# NRV-AOU34.net
KiCad netlist of a schematic drawn in Altium Designer
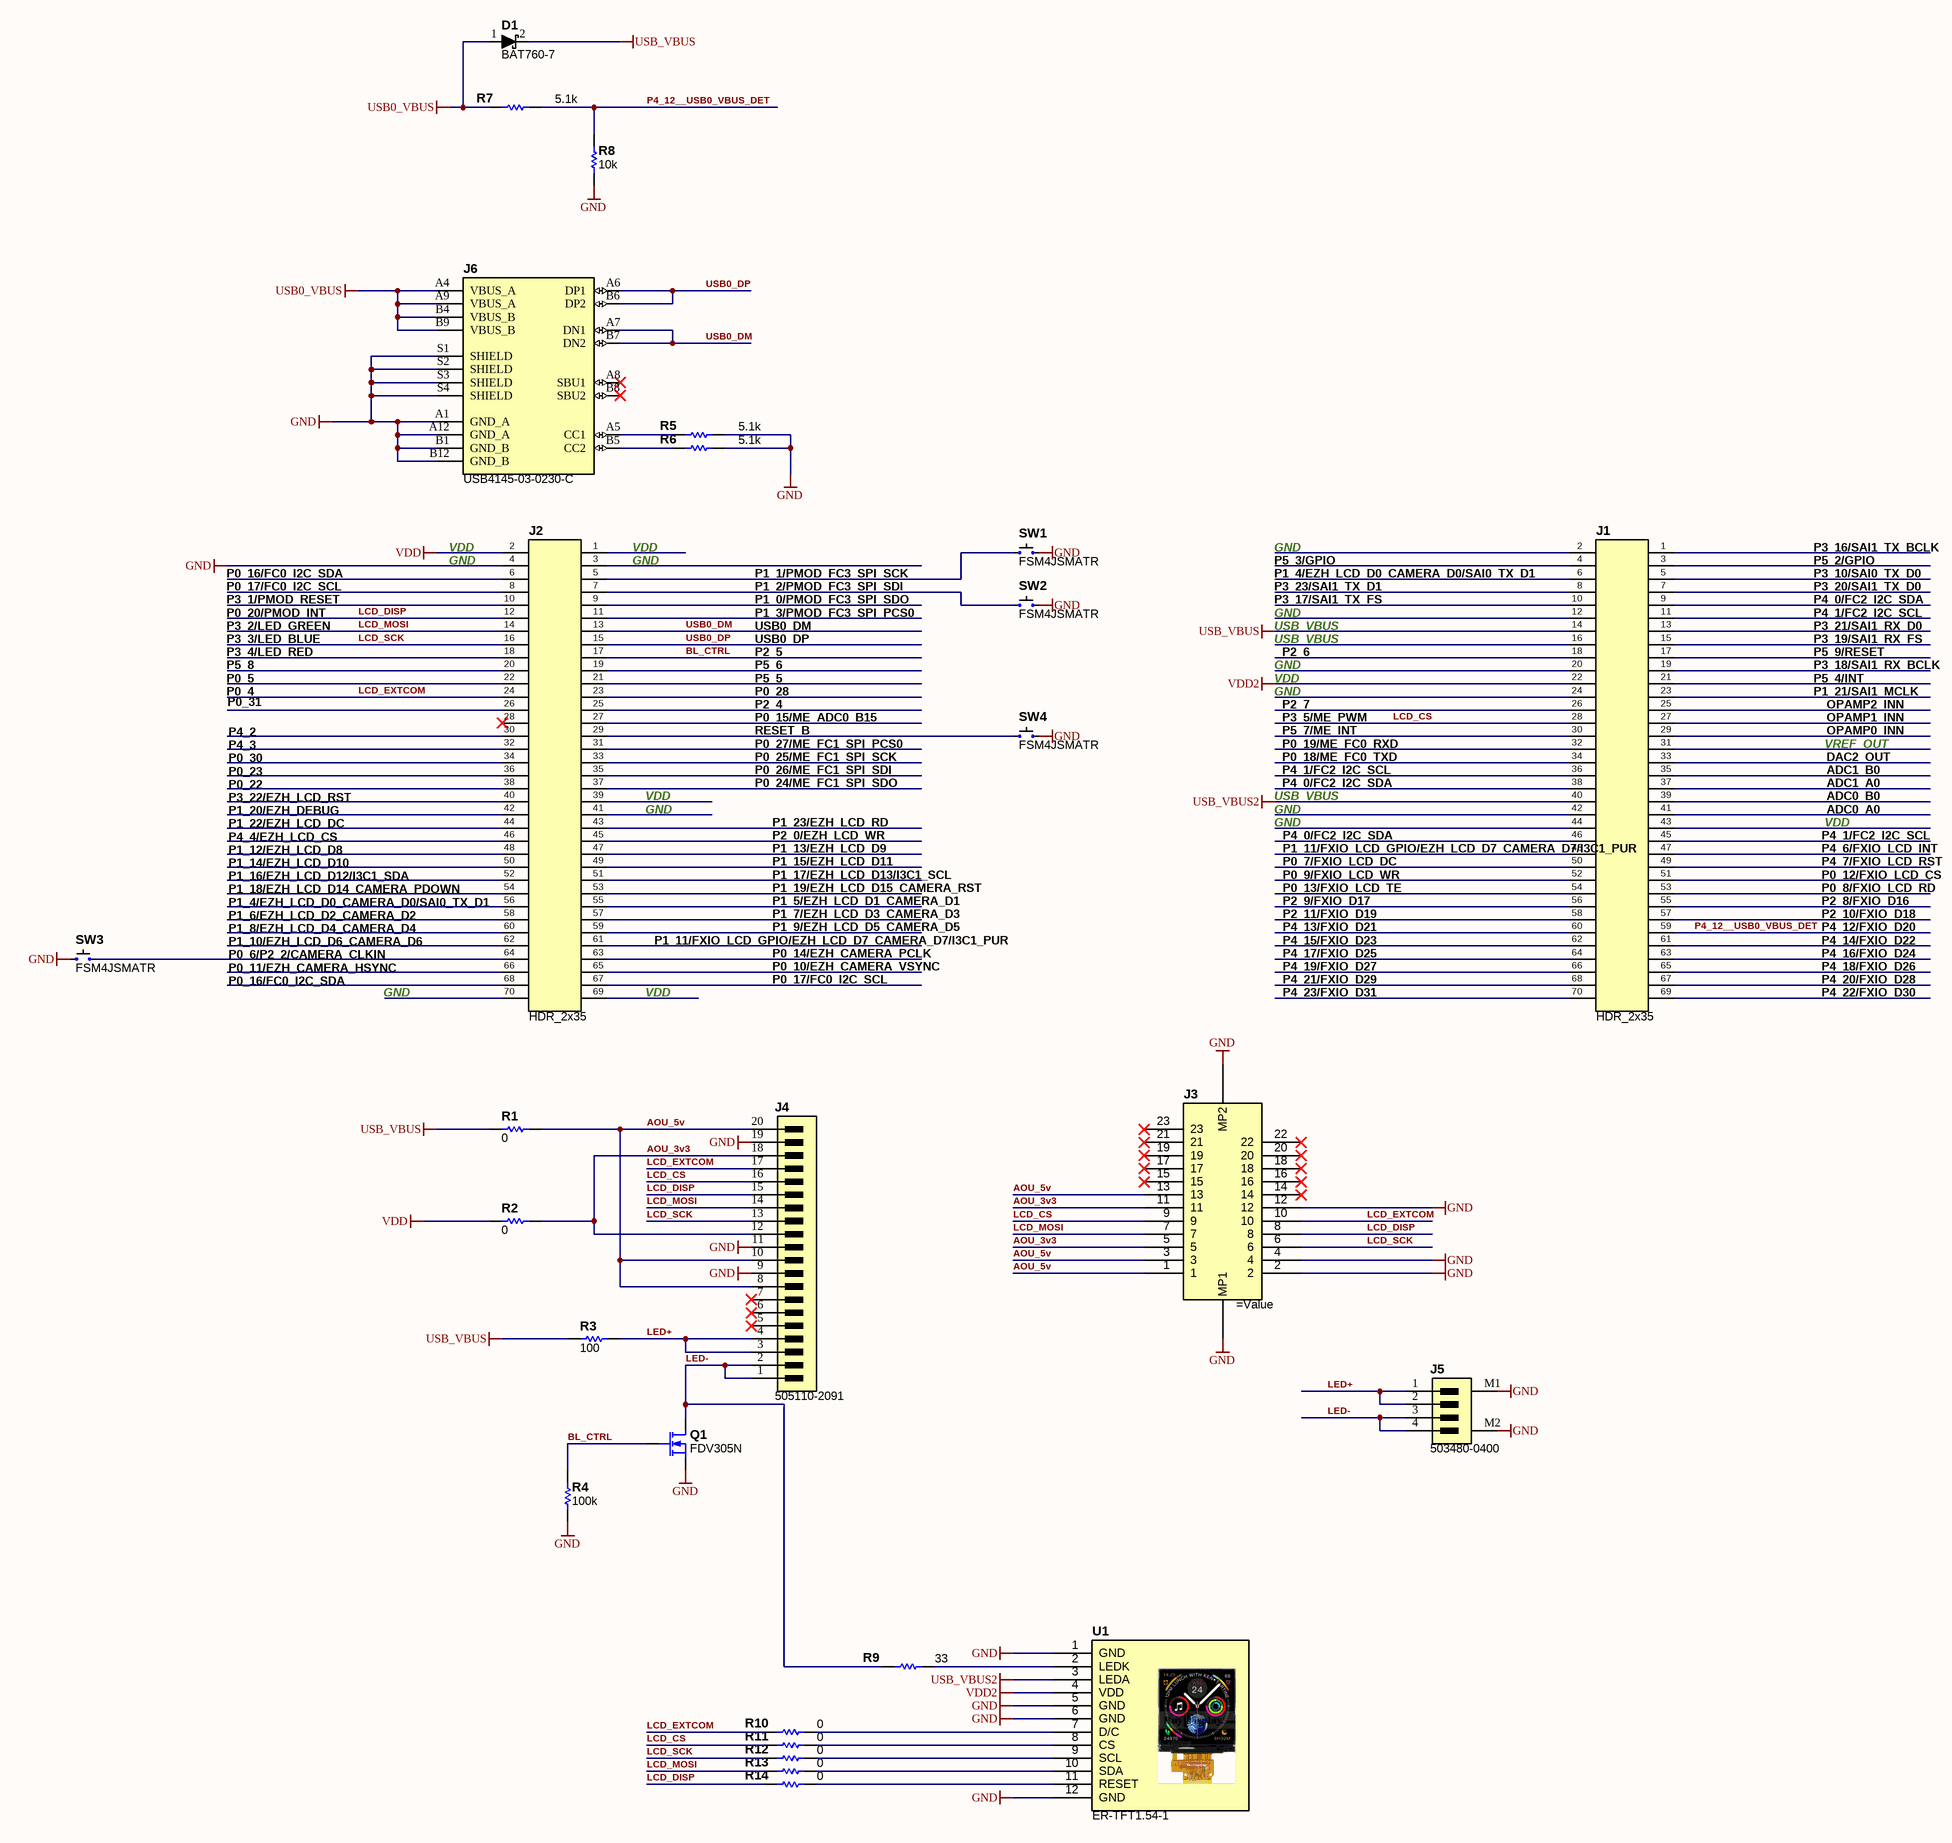
[diagram p0: NRV-AOU34.SchDoc]

(export (version "E")
  (design (tool "Eeschema 10.0.6"))
  (components
    (comp (ref "D1")
      (value "BAT760-7")
      (footprint "D_SOD-323_P")
      (description "DIODE SCHOTTKY 30V 1A SOD323")
      (fields (field (name "MANUFACTURER") "Diodes Inc"))
      (libsource (lib "Diodes") (part "DS_1A_2C"))
    )
    (comp (ref "J1")
      (value "HDR_2x35")
      (footprint "HEADER 2x35 .100\"")
      (description "2x35 Header .100\"")
      (libsource (lib "eConnector_Header") (part "HDR_2x35"))
    )
    (comp (ref "J2")
      (value "HDR_2x35")
      (footprint "HEADER 2x35 .100\"")
      (description "2x35 Header .100\"")
      (libsource (lib "eConnector_Header") (part "HDR_2x35"))
    )
    (comp (ref "J3")
      (value "~")
      (footprint "FH26W-23S-0.3SHW(60)")
      (fields
        (field (name "MANUFACTURER") "Hirose")
        (field (name "MANUFACTURER PART NUMBER") "FH26W-23S-0.3SHW(60)")
      )
      (libsource (lib "eConnector_FPC") (part "FH26W-23S-0.3SHW(60)"))
    )
    (comp (ref "J4")
      (value "505110-2091")
      (footprint "CON_5051102091_MOL")
      (description "Conn, Rect, Rt. Angle, FFC/FPC, 0.50MM Pitch, 20 Circuit, Bottom Contact, ZIF")
      (fields (field (name "MANUFACTURER") "Molex"))
      (libsource (lib "eConnector_FPC") (part "505110-2091"))
    )
    (comp (ref "J5")
      (value "503480-0400")
      (footprint "5034800400")
      (description "CONN FFC FPC 4POS 0.50MM R/A")
      (fields (field (name "MANUFACTURER") "Molex"))
      (libsource (lib "eConnector_FPC") (part "503480-0400"))
    )
    (comp (ref "J6")
      (value "USB4145-03-0230-C")
      (footprint "GCT_USB4145-03-0230-C_REVA2")
      (description "USB Connectors USB-C Rec 3u\" Vert 16P SMT 2.3mm TH stakes H7.46mm T+R+Cap")
      (fields (field (name "MANUFACTURER") "GCT"))
      (libsource (lib "eConnector_USB") (part "USB4145-03-0230-C"))
    )
    (comp (ref "Q1")
      (value "FDV305N")
      (footprint "SOT-23")
      (description "MOSFET N-CH 20V 0.9A SOT-23")
      (fields (field (name "MANUFACTURER") "Fairchild Semiconductor") (field (name "SOURCE") "Digikey"))
      (libsource (lib "eTransistor") (part "FDV305"))
    )
    (comp (ref "R1") (value "0") (footprint "R0603_0.55MM_MD") (libsource (lib "eResistors") (part "R")))
    (comp (ref "R2") (value "0") (footprint "R0603_0.55MM_MD") (libsource (lib "eResistors") (part "R")))
    (comp (ref "R3")
      (value "100")
      (footprint "R0805_0.65MM_MD")
      (description "0")
      (libsource (lib "eResistors") (part "R"))
    )
    (comp (ref "R4")
      (value "100k")
      (footprint "R0805_0.65MM_MD")
      (description "0")
      (libsource (lib "eResistors") (part "R"))
    )
    (comp (ref "R5")
      (value "5.1k")
      (footprint "R0603_0.55MM_MD")
      (description "0")
      (libsource (lib "eResistors") (part "R"))
    )
    (comp (ref "R6")
      (value "5.1k")
      (footprint "R0603_0.55MM_MD")
      (description "0")
      (libsource (lib "eResistors") (part "R"))
    )
    (comp (ref "R7")
      (value "5.1k")
      (footprint "R0603_0.55MM_MD")
      (description "0")
      (libsource (lib "eResistors") (part "R"))
    )
    (comp (ref "R8")
      (value "10k")
      (footprint "R0603_0.55MM_MD")
      (description "0")
      (libsource (lib "eResistors") (part "R"))
    )
    (comp (ref "R9")
      (value "33")
      (footprint "R0603_0.55MM_MD")
      (description "0")
      (libsource (lib "eResistors") (part "R"))
    )
    (comp (ref "R10") (value "0") (footprint "R0603_0.55MM_MD") (libsource (lib "eResistors") (part "R")))
    (comp (ref "R11") (value "0") (footprint "R0603_0.55MM_MD") (libsource (lib "eResistors") (part "R")))
    (comp (ref "R12") (value "0") (footprint "R0603_0.55MM_MD") (libsource (lib "eResistors") (part "R")))
    (comp (ref "R13") (value "0") (footprint "R0603_0.55MM_MD") (libsource (lib "eResistors") (part "R")))
    (comp (ref "R14") (value "0") (footprint "R0603_0.55MM_MD") (libsource (lib "eResistors") (part "R")))
    (comp (ref "SW1")
      (value "FSM4JSMATR")
      (footprint "FSM4JSMA")
      (description "SWITCH TACTILE SPST-NO 0.05A 12V")
      (fields (field (name "MANUFACTURER") "TE Connectivity"))
      (libsource (lib "eElectroMechanical") (part "FSM4JSMATR"))
    )
    (comp (ref "SW2")
      (value "FSM4JSMATR")
      (footprint "FSM4JSMA")
      (description "SWITCH TACTILE SPST-NO 0.05A 12V")
      (fields (field (name "MANUFACTURER") "TE Connectivity"))
      (libsource (lib "eElectroMechanical") (part "FSM4JSMATR"))
    )
    (comp (ref "SW3")
      (value "FSM4JSMATR")
      (footprint "FSM4JSMA")
      (description "SWITCH TACTILE SPST-NO 0.05A 12V")
      (fields (field (name "MANUFACTURER") "TE Connectivity"))
      (libsource (lib "") (part "FSM4JSMATR_1"))
    )
    (comp (ref "SW4")
      (value "FSM4JSMATR")
      (footprint "FSM4JSMA")
      (description "SWITCH TACTILE SPST-NO 0.05A 12V")
      (fields (field (name "MANUFACTURER") "TE Connectivity"))
      (libsource (lib "eElectroMechanical") (part "FSM4JSMATR"))
    )
    (comp (ref "U1")
      (value "ER-TFT1.54-1")
      (footprint "ER-TFT1.54-1")
      (description "1.54\" 240x240 IPS Display")
      (fields (field (name "MANUFACTURER") "Buy Display"))
      (libsource (lib "eDisplay") (part "ER-TFT1.54-1"))
    )
  )
  (nets
    (net (code "1") (name "/AOU_3v3") (class "Default")
      (node (ref "J3") (pin "11") (pinfunction "11_11") (pintype "passive"))
      (node (ref "J3") (pin "5") (pinfunction "5_5") (pintype "passive"))
      (node (ref "J4") (pin "12") (pinfunction "B1_12") (pintype "passive"))
      (node (ref "J4") (pin "18") (pinfunction "G2_18") (pintype "passive"))
      (node (ref "R2") (pin "2") (pinfunction "2_2") (pintype "passive"))
    )
    (net (code "2") (name "/AOU_5v") (class "Default")
      (node (ref "J3") (pin "1") (pinfunction "1_1") (pintype "passive"))
      (node (ref "J3") (pin "13") (pinfunction "13_13") (pintype "passive"))
      (node (ref "J3") (pin "3") (pinfunction "3_3") (pintype "passive"))
      (node (ref "J4") (pin "10") (pinfunction "B3_10") (pintype "passive"))
      (node (ref "J4") (pin "20") (pinfunction "G0_20") (pintype "passive"))
      (node (ref "J4") (pin "8") (pinfunction "B5_8") (pintype "passive"))
      (node (ref "R1") (pin "2") (pinfunction "2_2") (pintype "passive"))
    )
    (net (code "3") (name "/BL_CTRL") (class "Default")
      (node (ref "J2") (pin "17") (pinfunction "17_17") (pintype "passive"))
      (node (ref "Q1") (pin "1") (pinfunction "G_1") (pintype "passive"))
      (node (ref "R4") (pin "1") (pinfunction "1_1") (pintype "passive"))
    )
    (net (code "4") (name "/LCD_CS") (class "Default")
      (node (ref "J1") (pin "28") (pinfunction "28_28") (pintype "passive"))
      (node (ref "J3") (pin "9") (pinfunction "9_9") (pintype "passive"))
      (node (ref "J4") (pin "16") (pinfunction "G4_16") (pintype "passive"))
      (node (ref "R11") (pin "1") (pinfunction "1_1") (pintype "passive"))
    )
    (net (code "5") (name "/LCD_DISP") (class "Default")
      (node (ref "J2") (pin "12") (pinfunction "12_12") (pintype "passive"))
      (node (ref "J3") (pin "8") (pinfunction "8_8") (pintype "passive"))
      (node (ref "J4") (pin "15") (pinfunction "G5_15") (pintype "passive"))
      (node (ref "R14") (pin "1") (pinfunction "1_1") (pintype "passive"))
    )
    (net (code "6") (name "/LCD_EXTCOM") (class "Default")
      (node (ref "J2") (pin "24") (pinfunction "24_24") (pintype "passive"))
      (node (ref "J3") (pin "10") (pinfunction "10_10") (pintype "passive"))
      (node (ref "J4") (pin "17") (pinfunction "G3_17") (pintype "passive"))
      (node (ref "R10") (pin "1") (pinfunction "1_1") (pintype "passive"))
    )
    (net (code "7") (name "/LCD_MOSI") (class "Default")
      (node (ref "J2") (pin "14") (pinfunction "14_14") (pintype "passive"))
      (node (ref "J3") (pin "7") (pinfunction "7_7") (pintype "passive"))
      (node (ref "J4") (pin "14") (pinfunction "VSS_14") (pintype "passive"))
      (node (ref "R13") (pin "1") (pinfunction "1_1") (pintype "passive"))
    )
    (net (code "8") (name "/LCD_SCK") (class "Default")
      (node (ref "J2") (pin "16") (pinfunction "16_16") (pintype "passive"))
      (node (ref "J3") (pin "6") (pinfunction "6_6") (pintype "passive"))
      (node (ref "J4") (pin "13") (pinfunction "B0_13") (pintype "passive"))
      (node (ref "R12") (pin "1") (pinfunction "1_1") (pintype "passive"))
    )
    (net (code "9") (name "/LED+") (class "Default")
      (node (ref "J4") (pin "3") (pinfunction "VCC_3") (pintype "power_in"))
      (node (ref "J4") (pin "4") (pinfunction "VCC_4") (pintype "power_in"))
      (node (ref "J5") (pin "1") (pinfunction "VSS_1") (pintype "power_in"))
      (node (ref "J5") (pin "2") (pinfunction "VSS_2") (pintype "power_in"))
      (node (ref "R3") (pin "1") (pinfunction "1_1") (pintype "passive"))
    )
    (net (code "10") (name "/LED-") (class "Default")
      (node (ref "J4") (pin "1") (pinfunction "VSS_1") (pintype "power_in"))
      (node (ref "J4") (pin "2") (pinfunction "VSS_2") (pintype "power_in"))
      (node (ref "J5") (pin "3") (pinfunction "VCC_3") (pintype "power_in"))
      (node (ref "J5") (pin "4") (pinfunction "VCC_4") (pintype "power_in"))
      (node (ref "Q1") (pin "3") (pinfunction "D_3") (pintype "passive"))
      (node (ref "R9") (pin "1") (pinfunction "1_1") (pintype "passive"))
    )
    (net (code "11") (name "/P4_12__USB0_VBUS_DET") (class "Default")
      (node (ref "J1") (pin "59") (pinfunction "59_59") (pintype "passive"))
      (node (ref "R7") (pin "2") (pinfunction "2_2") (pintype "passive"))
      (node (ref "R8") (pin "2") (pinfunction "2_2") (pintype "passive"))
    )
    (net (code "12") (name "/USB0_DM") (class "Default")
      (node (ref "J2") (pin "13") (pinfunction "13_13") (pintype "passive"))
      (node (ref "J6") (pin "A7") (pinfunction "DN1_A7") (pintype "bidirectional"))
      (node (ref "J6") (pin "B7") (pinfunction "DN2_B7") (pintype "bidirectional"))
    )
    (net (code "13") (name "/USB0_DP") (class "Default")
      (node (ref "J2") (pin "15") (pinfunction "15_15") (pintype "passive"))
      (node (ref "J6") (pin "A6") (pinfunction "DP1_A6") (pintype "bidirectional"))
      (node (ref "J6") (pin "B6") (pinfunction "DP2_B6") (pintype "bidirectional"))
    )
    (net (code "14") (name "GND") (class "Default")
      (node (ref "J2") (pin "4") (pinfunction "4_4") (pintype "passive"))
      (node (ref "J3") (pin "12") (pinfunction "12_12") (pintype "passive"))
      (node (ref "J3") (pin "2") (pinfunction "2_2") (pintype "passive"))
      (node (ref "J3") (pin "4") (pinfunction "4_4") (pintype "passive"))
      (node (ref "J3") (pin "MP1") (pinfunction "MP1_MP1") (pintype "passive"))
      (node (ref "J3") (pin "MP2") (pinfunction "MP2_MP2") (pintype "passive"))
      (node (ref "J4") (pin "11") (pinfunction "B2_11") (pintype "passive"))
      (node (ref "J4") (pin "19") (pinfunction "G1_19") (pintype "passive"))
      (node (ref "J4") (pin "9") (pinfunction "B4_9") (pintype "passive"))
      (node (ref "J5") (pin "M1") (pinfunction "M1_M1") (pintype "power_in"))
      (node (ref "J5") (pin "M2") (pinfunction "M2_M2") (pintype "power_in"))
      (node (ref "J6") (pin "A1") (pinfunction "GND_A_A1") (pintype "power_in"))
      (node (ref "J6") (pin "A12") (pinfunction "GND_A_A12") (pintype "power_in"))
      (node (ref "J6") (pin "B1") (pinfunction "GND_B_B1") (pintype "power_in"))
      (node (ref "J6") (pin "B12") (pinfunction "GND_B_B12") (pintype "power_in"))
      (node (ref "J6") (pin "S1") (pinfunction "SHIELD_S1") (pintype "passive"))
      (node (ref "J6") (pin "S2") (pinfunction "SHIELD_S2") (pintype "passive"))
      (node (ref "J6") (pin "S3") (pinfunction "SHIELD_S3") (pintype "passive"))
      (node (ref "J6") (pin "S4") (pinfunction "SHIELD_S4") (pintype "passive"))
      (node (ref "Q1") (pin "2") (pinfunction "2_2") (pintype "passive"))
      (node (ref "R4") (pin "2") (pinfunction "2_2") (pintype "passive"))
      (node (ref "R5") (pin "2") (pinfunction "2_2") (pintype "passive"))
      (node (ref "R6") (pin "2") (pinfunction "2_2") (pintype "passive"))
      (node (ref "R8") (pin "1") (pinfunction "1_1") (pintype "passive"))
      (node (ref "SW1") (pin "A") (pinfunction "A_A") (pintype "passive"))
      (node (ref "SW2") (pin "A") (pinfunction "A_A") (pintype "passive"))
      (node (ref "SW3") (pin "A") (pinfunction "A_A") (pintype "passive"))
      (node (ref "SW4") (pin "A") (pinfunction "A_A") (pintype "passive"))
      (node (ref "U1") (pin "1") (pinfunction "GND_1") (pintype "passive"))
      (node (ref "U1") (pin "12") (pinfunction "GND_12") (pintype "passive"))
      (node (ref "U1") (pin "5") (pinfunction "GND_5") (pintype "passive"))
      (node (ref "U1") (pin "6") (pinfunction "GND_6") (pintype "passive"))
    )
    (net (code "15") (name "Net-(J2-Pad5)") (class "Default")
      (node (ref "J2") (pin "5") (pinfunction "5_5") (pintype "passive"))
      (node (ref "SW1") (pin "B") (pinfunction "B_B") (pintype "passive"))
    )
    (net (code "16") (name "Net-(J2-Pad7)") (class "Default")
      (node (ref "J2") (pin "7") (pinfunction "7_7") (pintype "passive"))
      (node (ref "SW2") (pin "B") (pinfunction "B_B") (pintype "passive"))
    )
    (net (code "17") (name "Net-(J2-Pad29)") (class "Default")
      (node (ref "J2") (pin "29") (pinfunction "29_29") (pintype "passive"))
      (node (ref "SW4") (pin "B") (pinfunction "B_B") (pintype "passive"))
    )
    (net (code "18") (name "Net-(J2-Pad64)") (class "Default")
      (node (ref "J2") (pin "64") (pinfunction "64_64") (pintype "passive"))
      (node (ref "SW3") (pin "B") (pinfunction "B_B") (pintype "passive"))
    )
    (net (code "19") (name "Net-(J6-CC1)") (class "Default")
      (node (ref "J6") (pin "A5") (pinfunction "CC1_A5") (pintype "bidirectional"))
      (node (ref "R5") (pin "1") (pinfunction "1_1") (pintype "passive"))
    )
    (net (code "20") (name "Net-(J6-CC2)") (class "Default")
      (node (ref "J6") (pin "B5") (pinfunction "CC2_B5") (pintype "bidirectional"))
      (node (ref "R6") (pin "1") (pinfunction "1_1") (pintype "passive"))
    )
    (net (code "21") (name "Net-(U1-CS)") (class "Default")
      (node (ref "R11") (pin "2") (pinfunction "2_2") (pintype "passive"))
      (node (ref "U1") (pin "8") (pinfunction "CS_8") (pintype "passive"))
    )
    (net (code "22") (name "Net-(U1-D{slash}C)") (class "Default")
      (node (ref "R10") (pin "2") (pinfunction "2_2") (pintype "passive"))
      (node (ref "U1") (pin "7") (pinfunction "D/C_7") (pintype "passive"))
    )
    (net (code "23") (name "Net-(U1-LEDK)") (class "Default")
      (node (ref "R9") (pin "2") (pinfunction "2_2") (pintype "passive"))
      (node (ref "U1") (pin "2") (pinfunction "LEDK_2") (pintype "passive"))
    )
    (net (code "24") (name "Net-(U1-RESET)") (class "Default")
      (node (ref "R14") (pin "2") (pinfunction "2_2") (pintype "passive"))
      (node (ref "U1") (pin "11") (pinfunction "RESET_11") (pintype "passive"))
    )
    (net (code "25") (name "Net-(U1-SCL)") (class "Default")
      (node (ref "R12") (pin "2") (pinfunction "2_2") (pintype "passive"))
      (node (ref "U1") (pin "9") (pinfunction "SCL_9") (pintype "passive"))
    )
    (net (code "26") (name "Net-(U1-SDA)") (class "Default")
      (node (ref "R13") (pin "2") (pinfunction "2_2") (pintype "passive"))
      (node (ref "U1") (pin "10") (pinfunction "SDA_10") (pintype "passive"))
    )
    (net (code "27") (name "USB0_VBUS") (class "Default")
      (node (ref "D1") (pin "1") (pinfunction "A_1") (pintype "passive"))
      (node (ref "J6") (pin "A4") (pinfunction "VBUS_A_A4") (pintype "power_in"))
      (node (ref "J6") (pin "A9") (pinfunction "VBUS_A_A9") (pintype "power_in"))
      (node (ref "J6") (pin "B4") (pinfunction "VBUS_B_B4") (pintype "power_in"))
      (node (ref "J6") (pin "B9") (pinfunction "VBUS_B_B9") (pintype "power_in"))
      (node (ref "R7") (pin "1") (pinfunction "1_1") (pintype "passive"))
    )
    (net (code "28") (name "USB_VBUS") (class "Default")
      (node (ref "D1") (pin "2") (pinfunction "K_2") (pintype "passive"))
      (node (ref "J1") (pin "14") (pinfunction "14_14") (pintype "passive"))
      (node (ref "R1") (pin "1") (pinfunction "1_1") (pintype "passive"))
      (node (ref "R3") (pin "2") (pinfunction "2_2") (pintype "passive"))
    )
    (net (code "29") (name "USB_VBUS2") (class "Default")
      (node (ref "J1") (pin "40") (pinfunction "40_40") (pintype "passive"))
      (node (ref "U1") (pin "3") (pinfunction "LEDA_3") (pintype "passive"))
    )
    (net (code "30") (name "VDD") (class "Default")
      (node (ref "J2") (pin "2") (pinfunction "2_2") (pintype "passive"))
      (node (ref "R2") (pin "1") (pinfunction "1_1") (pintype "passive"))
    )
    (net (code "31") (name "VDD2") (class "Default")
      (node (ref "J1") (pin "22") (pinfunction "22_22") (pintype "passive"))
      (node (ref "U1") (pin "4") (pinfunction "VDD_4") (pintype "passive"))
    )
    (net (code "32") (name "unconnected-(J1-Pad1)") (class "Default")
      (node (ref "J1") (pin "1") (pinfunction "1_1") (pintype "passive"))
    )
    (net (code "33") (name "unconnected-(J1-Pad2)") (class "Default")
      (node (ref "J1") (pin "2") (pinfunction "2_2") (pintype "passive"))
    )
    (net (code "34") (name "unconnected-(J1-Pad3)") (class "Default")
      (node (ref "J1") (pin "3") (pinfunction "3_3") (pintype "passive"))
    )
    (net (code "35") (name "unconnected-(J1-Pad4)") (class "Default")
      (node (ref "J1") (pin "4") (pinfunction "4_4") (pintype "passive"))
    )
    (net (code "36") (name "unconnected-(J1-Pad5)") (class "Default")
      (node (ref "J1") (pin "5") (pinfunction "5_5") (pintype "passive"))
    )
    (net (code "37") (name "unconnected-(J1-Pad6)") (class "Default")
      (node (ref "J1") (pin "6") (pinfunction "6_6") (pintype "passive"))
    )
    (net (code "38") (name "unconnected-(J1-Pad7)") (class "Default")
      (node (ref "J1") (pin "7") (pinfunction "7_7") (pintype "passive"))
    )
    (net (code "39") (name "unconnected-(J1-Pad8)") (class "Default")
      (node (ref "J1") (pin "8") (pinfunction "8_8") (pintype "passive"))
    )
    (net (code "40") (name "unconnected-(J1-Pad9)") (class "Default")
      (node (ref "J1") (pin "9") (pinfunction "9_9") (pintype "passive"))
    )
    (net (code "41") (name "unconnected-(J1-Pad10)") (class "Default")
      (node (ref "J1") (pin "10") (pinfunction "10_10") (pintype "passive"))
    )
    (net (code "42") (name "unconnected-(J1-Pad11)") (class "Default")
      (node (ref "J1") (pin "11") (pinfunction "11_11") (pintype "passive"))
    )
    (net (code "43") (name "unconnected-(J1-Pad12)") (class "Default")
      (node (ref "J1") (pin "12") (pinfunction "12_12") (pintype "passive"))
    )
    (net (code "44") (name "unconnected-(J1-Pad13)") (class "Default")
      (node (ref "J1") (pin "13") (pinfunction "13_13") (pintype "passive"))
    )
    (net (code "45") (name "unconnected-(J1-Pad15)") (class "Default")
      (node (ref "J1") (pin "15") (pinfunction "15_15") (pintype "passive"))
    )
    (net (code "46") (name "unconnected-(J1-Pad16)") (class "Default")
      (node (ref "J1") (pin "16") (pinfunction "16_16") (pintype "passive"))
    )
    (net (code "47") (name "unconnected-(J1-Pad17)") (class "Default")
      (node (ref "J1") (pin "17") (pinfunction "17_17") (pintype "passive"))
    )
    (net (code "48") (name "unconnected-(J1-Pad18)") (class "Default")
      (node (ref "J1") (pin "18") (pinfunction "18_18") (pintype "passive"))
    )
    (net (code "49") (name "unconnected-(J1-Pad19)") (class "Default")
      (node (ref "J1") (pin "19") (pinfunction "19_19") (pintype "passive"))
    )
    (net (code "50") (name "unconnected-(J1-Pad20)") (class "Default")
      (node (ref "J1") (pin "20") (pinfunction "20_20") (pintype "passive"))
    )
    (net (code "51") (name "unconnected-(J1-Pad21)") (class "Default")
      (node (ref "J1") (pin "21") (pinfunction "21_21") (pintype "passive"))
    )
    (net (code "52") (name "unconnected-(J1-Pad23)") (class "Default")
      (node (ref "J1") (pin "23") (pinfunction "23_23") (pintype "passive"))
    )
    (net (code "53") (name "unconnected-(J1-Pad24)") (class "Default")
      (node (ref "J1") (pin "24") (pinfunction "24_24") (pintype "passive"))
    )
    (net (code "54") (name "unconnected-(J1-Pad25)") (class "Default")
      (node (ref "J1") (pin "25") (pinfunction "25_25") (pintype "passive"))
    )
    (net (code "55") (name "unconnected-(J1-Pad26)") (class "Default")
      (node (ref "J1") (pin "26") (pinfunction "26_26") (pintype "passive"))
    )
    (net (code "56") (name "unconnected-(J1-Pad27)") (class "Default")
      (node (ref "J1") (pin "27") (pinfunction "27_27") (pintype "passive"))
    )
    (net (code "57") (name "unconnected-(J1-Pad29)") (class "Default")
      (node (ref "J1") (pin "29") (pinfunction "29_29") (pintype "passive"))
    )
    (net (code "58") (name "unconnected-(J1-Pad30)") (class "Default")
      (node (ref "J1") (pin "30") (pinfunction "30_30") (pintype "passive"))
    )
    (net (code "59") (name "unconnected-(J1-Pad31)") (class "Default")
      (node (ref "J1") (pin "31") (pinfunction "31_31") (pintype "passive"))
    )
    (net (code "60") (name "unconnected-(J1-Pad32)") (class "Default")
      (node (ref "J1") (pin "32") (pinfunction "32_32") (pintype "passive"))
    )
    (net (code "61") (name "unconnected-(J1-Pad33)") (class "Default")
      (node (ref "J1") (pin "33") (pinfunction "33_33") (pintype "passive"))
    )
    (net (code "62") (name "unconnected-(J1-Pad34)") (class "Default")
      (node (ref "J1") (pin "34") (pinfunction "34_34") (pintype "passive"))
    )
    (net (code "63") (name "unconnected-(J1-Pad35)") (class "Default")
      (node (ref "J1") (pin "35") (pinfunction "35_35") (pintype "passive"))
    )
    (net (code "64") (name "unconnected-(J1-Pad36)") (class "Default")
      (node (ref "J1") (pin "36") (pinfunction "36_36") (pintype "passive"))
    )
    (net (code "65") (name "unconnected-(J1-Pad37)") (class "Default")
      (node (ref "J1") (pin "37") (pinfunction "37_37") (pintype "passive"))
    )
    (net (code "66") (name "unconnected-(J1-Pad38)") (class "Default")
      (node (ref "J1") (pin "38") (pinfunction "38_38") (pintype "passive"))
    )
    (net (code "67") (name "unconnected-(J1-Pad39)") (class "Default")
      (node (ref "J1") (pin "39") (pinfunction "39_39") (pintype "passive"))
    )
    (net (code "68") (name "unconnected-(J1-Pad41)") (class "Default")
      (node (ref "J1") (pin "41") (pinfunction "41_41") (pintype "passive"))
    )
    (net (code "69") (name "unconnected-(J1-Pad42)") (class "Default")
      (node (ref "J1") (pin "42") (pinfunction "42_42") (pintype "passive"))
    )
    (net (code "70") (name "unconnected-(J1-Pad43)") (class "Default")
      (node (ref "J1") (pin "43") (pinfunction "43_43") (pintype "passive"))
    )
    (net (code "71") (name "unconnected-(J1-Pad44)") (class "Default")
      (node (ref "J1") (pin "44") (pinfunction "44_44") (pintype "passive"))
    )
    (net (code "72") (name "unconnected-(J1-Pad45)") (class "Default")
      (node (ref "J1") (pin "45") (pinfunction "45_45") (pintype "passive"))
    )
    (net (code "73") (name "unconnected-(J1-Pad46)") (class "Default")
      (node (ref "J1") (pin "46") (pinfunction "46_46") (pintype "passive"))
    )
    (net (code "74") (name "unconnected-(J1-Pad47)") (class "Default")
      (node (ref "J1") (pin "47") (pinfunction "47_47") (pintype "passive"))
    )
    (net (code "75") (name "unconnected-(J1-Pad48)") (class "Default")
      (node (ref "J1") (pin "48") (pinfunction "48_48") (pintype "passive"))
    )
    (net (code "76") (name "unconnected-(J1-Pad49)") (class "Default")
      (node (ref "J1") (pin "49") (pinfunction "49_49") (pintype "passive"))
    )
    (net (code "77") (name "unconnected-(J1-Pad50)") (class "Default")
      (node (ref "J1") (pin "50") (pinfunction "50_50") (pintype "passive"))
    )
    (net (code "78") (name "unconnected-(J1-Pad51)") (class "Default")
      (node (ref "J1") (pin "51") (pinfunction "51_51") (pintype "passive"))
    )
    (net (code "79") (name "unconnected-(J1-Pad52)") (class "Default")
      (node (ref "J1") (pin "52") (pinfunction "52_52") (pintype "passive"))
    )
    (net (code "80") (name "unconnected-(J1-Pad53)") (class "Default")
      (node (ref "J1") (pin "53") (pinfunction "53_53") (pintype "passive"))
    )
    (net (code "81") (name "unconnected-(J1-Pad54)") (class "Default")
      (node (ref "J1") (pin "54") (pinfunction "54_54") (pintype "passive"))
    )
    (net (code "82") (name "unconnected-(J1-Pad55)") (class "Default")
      (node (ref "J1") (pin "55") (pinfunction "55_55") (pintype "passive"))
    )
    (net (code "83") (name "unconnected-(J1-Pad56)") (class "Default")
      (node (ref "J1") (pin "56") (pinfunction "56_56") (pintype "passive"))
    )
    (net (code "84") (name "unconnected-(J1-Pad57)") (class "Default")
      (node (ref "J1") (pin "57") (pinfunction "57_57") (pintype "passive"))
    )
    (net (code "85") (name "unconnected-(J1-Pad58)") (class "Default")
      (node (ref "J1") (pin "58") (pinfunction "58_58") (pintype "passive"))
    )
    (net (code "86") (name "unconnected-(J1-Pad60)") (class "Default")
      (node (ref "J1") (pin "60") (pinfunction "60_60") (pintype "passive"))
    )
    (net (code "87") (name "unconnected-(J1-Pad61)") (class "Default")
      (node (ref "J1") (pin "61") (pinfunction "61_61") (pintype "passive"))
    )
    (net (code "88") (name "unconnected-(J1-Pad62)") (class "Default")
      (node (ref "J1") (pin "62") (pinfunction "62_62") (pintype "passive"))
    )
    (net (code "89") (name "unconnected-(J1-Pad63)") (class "Default")
      (node (ref "J1") (pin "63") (pinfunction "63_63") (pintype "passive"))
    )
    (net (code "90") (name "unconnected-(J1-Pad64)") (class "Default")
      (node (ref "J1") (pin "64") (pinfunction "64_64") (pintype "passive"))
    )
    (net (code "91") (name "unconnected-(J1-Pad65)") (class "Default")
      (node (ref "J1") (pin "65") (pinfunction "65_65") (pintype "passive"))
    )
    (net (code "92") (name "unconnected-(J1-Pad66)") (class "Default")
      (node (ref "J1") (pin "66") (pinfunction "66_66") (pintype "passive"))
    )
    (net (code "93") (name "unconnected-(J1-Pad67)") (class "Default")
      (node (ref "J1") (pin "67") (pinfunction "67_67") (pintype "passive"))
    )
    (net (code "94") (name "unconnected-(J1-Pad68)") (class "Default")
      (node (ref "J1") (pin "68") (pinfunction "68_68") (pintype "passive"))
    )
    (net (code "95") (name "unconnected-(J1-Pad69)") (class "Default")
      (node (ref "J1") (pin "69") (pinfunction "69_69") (pintype "passive"))
    )
    (net (code "96") (name "unconnected-(J1-Pad70)") (class "Default")
      (node (ref "J1") (pin "70") (pinfunction "70_70") (pintype "passive"))
    )
    (net (code "97") (name "unconnected-(J2-Pad1)") (class "Default")
      (node (ref "J2") (pin "1") (pinfunction "1_1") (pintype "passive"))
    )
    (net (code "98") (name "unconnected-(J2-Pad3)") (class "Default")
      (node (ref "J2") (pin "3") (pinfunction "3_3") (pintype "passive"))
    )
    (net (code "99") (name "unconnected-(J2-Pad6)") (class "Default")
      (node (ref "J2") (pin "6") (pinfunction "6_6") (pintype "passive"))
    )
    (net (code "100") (name "unconnected-(J2-Pad8)") (class "Default")
      (node (ref "J2") (pin "8") (pinfunction "8_8") (pintype "passive"))
    )
    (net (code "101") (name "unconnected-(J2-Pad9)") (class "Default")
      (node (ref "J2") (pin "9") (pinfunction "9_9") (pintype "passive"))
    )
    (net (code "102") (name "unconnected-(J2-Pad10)") (class "Default")
      (node (ref "J2") (pin "10") (pinfunction "10_10") (pintype "passive"))
    )
    (net (code "103") (name "unconnected-(J2-Pad11)") (class "Default")
      (node (ref "J2") (pin "11") (pinfunction "11_11") (pintype "passive"))
    )
    (net (code "104") (name "unconnected-(J2-Pad18)") (class "Default")
      (node (ref "J2") (pin "18") (pinfunction "18_18") (pintype "passive"))
    )
    (net (code "105") (name "unconnected-(J2-Pad19)") (class "Default")
      (node (ref "J2") (pin "19") (pinfunction "19_19") (pintype "passive"))
    )
    (net (code "106") (name "unconnected-(J2-Pad20)") (class "Default")
      (node (ref "J2") (pin "20") (pinfunction "20_20") (pintype "passive"))
    )
    (net (code "107") (name "unconnected-(J2-Pad21)") (class "Default")
      (node (ref "J2") (pin "21") (pinfunction "21_21") (pintype "passive"))
    )
    (net (code "108") (name "unconnected-(J2-Pad22)") (class "Default")
      (node (ref "J2") (pin "22") (pinfunction "22_22") (pintype "passive"))
    )
    (net (code "109") (name "unconnected-(J2-Pad23)") (class "Default")
      (node (ref "J2") (pin "23") (pinfunction "23_23") (pintype "passive"))
    )
    (net (code "110") (name "unconnected-(J2-Pad25)") (class "Default")
      (node (ref "J2") (pin "25") (pinfunction "25_25") (pintype "passive"))
    )
    (net (code "111") (name "unconnected-(J2-Pad26)") (class "Default")
      (node (ref "J2") (pin "26") (pinfunction "26_26") (pintype "passive"))
    )
    (net (code "112") (name "unconnected-(J2-Pad27)") (class "Default")
      (node (ref "J2") (pin "27") (pinfunction "27_27") (pintype "passive"))
    )
    (net (code "113") (name "unconnected-(J2-Pad28)") (class "Default")
      (node (ref "J2") (pin "28") (pinfunction "28_28") (pintype "passive+no_connect"))
    )
    (net (code "114") (name "unconnected-(J2-Pad30)") (class "Default")
      (node (ref "J2") (pin "30") (pinfunction "30_30") (pintype "passive"))
    )
    (net (code "115") (name "unconnected-(J2-Pad31)") (class "Default")
      (node (ref "J2") (pin "31") (pinfunction "31_31") (pintype "passive"))
    )
    (net (code "116") (name "unconnected-(J2-Pad32)") (class "Default")
      (node (ref "J2") (pin "32") (pinfunction "32_32") (pintype "passive"))
    )
    (net (code "117") (name "unconnected-(J2-Pad33)") (class "Default")
      (node (ref "J2") (pin "33") (pinfunction "33_33") (pintype "passive"))
    )
    (net (code "118") (name "unconnected-(J2-Pad34)") (class "Default")
      (node (ref "J2") (pin "34") (pinfunction "34_34") (pintype "passive"))
    )
    (net (code "119") (name "unconnected-(J2-Pad35)") (class "Default")
      (node (ref "J2") (pin "35") (pinfunction "35_35") (pintype "passive"))
    )
    (net (code "120") (name "unconnected-(J2-Pad36)") (class "Default")
      (node (ref "J2") (pin "36") (pinfunction "36_36") (pintype "passive"))
    )
    (net (code "121") (name "unconnected-(J2-Pad37)") (class "Default")
      (node (ref "J2") (pin "37") (pinfunction "37_37") (pintype "passive"))
    )
    (net (code "122") (name "unconnected-(J2-Pad38)") (class "Default")
      (node (ref "J2") (pin "38") (pinfunction "38_38") (pintype "passive"))
    )
    (net (code "123") (name "unconnected-(J2-Pad39)") (class "Default")
      (node (ref "J2") (pin "39") (pinfunction "39_39") (pintype "passive"))
    )
    (net (code "124") (name "unconnected-(J2-Pad40)") (class "Default")
      (node (ref "J2") (pin "40") (pinfunction "40_40") (pintype "passive"))
    )
    (net (code "125") (name "unconnected-(J2-Pad41)") (class "Default")
      (node (ref "J2") (pin "41") (pinfunction "41_41") (pintype "passive"))
    )
    (net (code "126") (name "unconnected-(J2-Pad42)") (class "Default")
      (node (ref "J2") (pin "42") (pinfunction "42_42") (pintype "passive"))
    )
    (net (code "127") (name "unconnected-(J2-Pad43)") (class "Default")
      (node (ref "J2") (pin "43") (pinfunction "43_43") (pintype "passive"))
    )
    (net (code "128") (name "unconnected-(J2-Pad44)") (class "Default")
      (node (ref "J2") (pin "44") (pinfunction "44_44") (pintype "passive"))
    )
    (net (code "129") (name "unconnected-(J2-Pad45)") (class "Default")
      (node (ref "J2") (pin "45") (pinfunction "45_45") (pintype "passive"))
    )
    (net (code "130") (name "unconnected-(J2-Pad46)") (class "Default")
      (node (ref "J2") (pin "46") (pinfunction "46_46") (pintype "passive"))
    )
    (net (code "131") (name "unconnected-(J2-Pad47)") (class "Default")
      (node (ref "J2") (pin "47") (pinfunction "47_47") (pintype "passive"))
    )
    (net (code "132") (name "unconnected-(J2-Pad48)") (class "Default")
      (node (ref "J2") (pin "48") (pinfunction "48_48") (pintype "passive"))
    )
    (net (code "133") (name "unconnected-(J2-Pad49)") (class "Default")
      (node (ref "J2") (pin "49") (pinfunction "49_49") (pintype "passive"))
    )
    (net (code "134") (name "unconnected-(J2-Pad50)") (class "Default")
      (node (ref "J2") (pin "50") (pinfunction "50_50") (pintype "passive"))
    )
    (net (code "135") (name "unconnected-(J2-Pad51)") (class "Default")
      (node (ref "J2") (pin "51") (pinfunction "51_51") (pintype "passive"))
    )
    (net (code "136") (name "unconnected-(J2-Pad52)") (class "Default")
      (node (ref "J2") (pin "52") (pinfunction "52_52") (pintype "passive"))
    )
    (net (code "137") (name "unconnected-(J2-Pad53)") (class "Default")
      (node (ref "J2") (pin "53") (pinfunction "53_53") (pintype "passive"))
    )
    (net (code "138") (name "unconnected-(J2-Pad54)") (class "Default")
      (node (ref "J2") (pin "54") (pinfunction "54_54") (pintype "passive"))
    )
    (net (code "139") (name "unconnected-(J2-Pad55)") (class "Default")
      (node (ref "J2") (pin "55") (pinfunction "55_55") (pintype "passive"))
    )
    (net (code "140") (name "unconnected-(J2-Pad56)") (class "Default")
      (node (ref "J2") (pin "56") (pinfunction "56_56") (pintype "passive"))
    )
    (net (code "141") (name "unconnected-(J2-Pad57)") (class "Default")
      (node (ref "J2") (pin "57") (pinfunction "57_57") (pintype "passive"))
    )
    (net (code "142") (name "unconnected-(J2-Pad58)") (class "Default")
      (node (ref "J2") (pin "58") (pinfunction "58_58") (pintype "passive"))
    )
    (net (code "143") (name "unconnected-(J2-Pad59)") (class "Default")
      (node (ref "J2") (pin "59") (pinfunction "59_59") (pintype "passive"))
    )
    (net (code "144") (name "unconnected-(J2-Pad60)") (class "Default")
      (node (ref "J2") (pin "60") (pinfunction "60_60") (pintype "passive"))
    )
    (net (code "145") (name "unconnected-(J2-Pad61)") (class "Default")
      (node (ref "J2") (pin "61") (pinfunction "61_61") (pintype "passive"))
    )
    (net (code "146") (name "unconnected-(J2-Pad62)") (class "Default")
      (node (ref "J2") (pin "62") (pinfunction "62_62") (pintype "passive"))
    )
    (net (code "147") (name "unconnected-(J2-Pad63)") (class "Default")
      (node (ref "J2") (pin "63") (pinfunction "63_63") (pintype "passive"))
    )
    (net (code "148") (name "unconnected-(J2-Pad65)") (class "Default")
      (node (ref "J2") (pin "65") (pinfunction "65_65") (pintype "passive"))
    )
    (net (code "149") (name "unconnected-(J2-Pad66)") (class "Default")
      (node (ref "J2") (pin "66") (pinfunction "66_66") (pintype "passive"))
    )
    (net (code "150") (name "unconnected-(J2-Pad67)") (class "Default")
      (node (ref "J2") (pin "67") (pinfunction "67_67") (pintype "passive"))
    )
    (net (code "151") (name "unconnected-(J2-Pad68)") (class "Default")
      (node (ref "J2") (pin "68") (pinfunction "68_68") (pintype "passive"))
    )
    (net (code "152") (name "unconnected-(J2-Pad69)") (class "Default")
      (node (ref "J2") (pin "69") (pinfunction "69_69") (pintype "passive"))
    )
    (net (code "153") (name "unconnected-(J2-Pad70)") (class "Default")
      (node (ref "J2") (pin "70") (pinfunction "70_70") (pintype "passive"))
    )
    (net (code "154") (name "unconnected-(J3-Pad14)") (class "Default")
      (node (ref "J3") (pin "14") (pinfunction "14_14") (pintype "passive+no_connect"))
    )
    (net (code "155") (name "unconnected-(J3-Pad15)") (class "Default")
      (node (ref "J3") (pin "15") (pinfunction "15_15") (pintype "passive+no_connect"))
    )
    (net (code "156") (name "unconnected-(J3-Pad16)") (class "Default")
      (node (ref "J3") (pin "16") (pinfunction "16_16") (pintype "passive+no_connect"))
    )
    (net (code "157") (name "unconnected-(J3-Pad17)") (class "Default")
      (node (ref "J3") (pin "17") (pinfunction "17_17") (pintype "passive+no_connect"))
    )
    (net (code "158") (name "unconnected-(J3-Pad18)") (class "Default")
      (node (ref "J3") (pin "18") (pinfunction "18_18") (pintype "passive+no_connect"))
    )
    (net (code "159") (name "unconnected-(J3-Pad19)") (class "Default")
      (node (ref "J3") (pin "19") (pinfunction "19_19") (pintype "passive+no_connect"))
    )
    (net (code "160") (name "unconnected-(J3-Pad20)") (class "Default")
      (node (ref "J3") (pin "20") (pinfunction "20_20") (pintype "passive+no_connect"))
    )
    (net (code "161") (name "unconnected-(J3-Pad21)") (class "Default")
      (node (ref "J3") (pin "21") (pinfunction "21_21") (pintype "passive+no_connect"))
    )
    (net (code "162") (name "unconnected-(J3-Pad22)") (class "Default")
      (node (ref "J3") (pin "22") (pinfunction "22_22") (pintype "passive+no_connect"))
    )
    (net (code "163") (name "unconnected-(J3-Pad23)") (class "Default")
      (node (ref "J3") (pin "23") (pinfunction "23_23") (pintype "passive+no_connect"))
    )
    (net (code "164") (name "unconnected-(J4-LEDCTRL-Pad6)") (class "Default")
      (node (ref "J4") (pin "6") (pinfunction "LEDCTRL_6") (pintype "passive+no_connect"))
    )
    (net (code "165") (name "unconnected-(J4-PWCTRL-Pad5)") (class "Default")
      (node (ref "J4") (pin "5") (pinfunction "PWCTRL_5") (pintype "passive+no_connect"))
    )
    (net (code "166") (name "unconnected-(J4-RESET#-Pad7)") (class "Default")
      (node (ref "J4") (pin "7") (pinfunction "RESET#_7") (pintype "passive+no_connect"))
    )
    (net (code "167") (name "unconnected-(J6-SBU1-PadA8)") (class "Default")
      (node (ref "J6") (pin "A8") (pinfunction "SBU1_A8") (pintype "bidirectional+no_connect"))
    )
    (net (code "168") (name "unconnected-(J6-SBU2-PadB8)") (class "Default")
      (node (ref "J6") (pin "B8") (pinfunction "SBU2_B8") (pintype "bidirectional+no_connect"))
    )
  )
)
